# flipflop-edgedetect.net
KiCad netlist of a schematic drawn in EAGLE
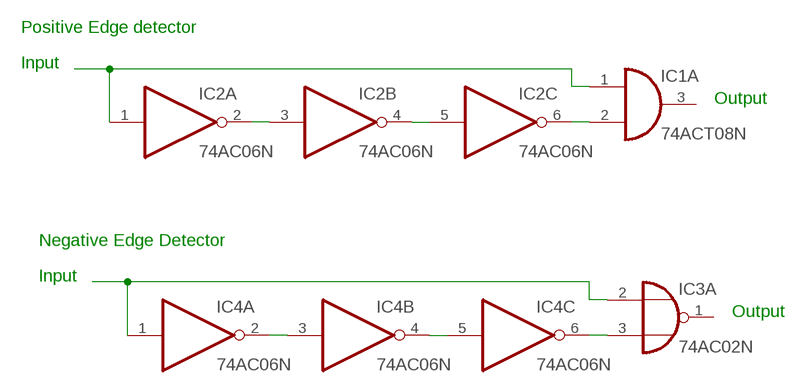
[diagram p0: schematic, sheet 1]

(export (version "E")
  (design (tool "Eeschema 10.0.6"))
  (components
    (comp (ref "IC1")
      (value "74ACT08N")
      (footprint "eagle-import:DIL14")
      (libsource (lib "eagle-import") (part "7408NACT"))
    )
    (comp (ref "IC2")
      (value "74AC06N")
      (footprint "eagle-import:DIL14")
      (libsource (lib "eagle-import") (part "7406NAC"))
    )
    (comp (ref "IC3")
      (value "74AC02N")
      (footprint "eagle-import:DIL14")
      (libsource (lib "eagle-import") (part "7402NAC"))
    )
    (comp (ref "IC4")
      (value "74AC06N")
      (footprint "eagle-import:DIL14")
      (libsource (lib "eagle-import") (part "7406NAC"))
    )
  )
  (nets
    (net (code "1") (name "Net-(IC1A-I0)") (class "Default")
      (node (ref "IC1") (pin "1") (pinfunction "I0_1") (pintype "input"))
      (node (ref "IC2") (pin "1") (pinfunction "I_1") (pintype "input"))
    )
    (net (code "2") (name "Net-(IC1A-I1)") (class "Default")
      (node (ref "IC1") (pin "2") (pinfunction "I1_2") (pintype "input"))
      (node (ref "IC2") (pin "6") (pinfunction "O_6") (pintype "open_collector"))
    )
    (net (code "3") (name "Net-(IC2A-O)") (class "Default")
      (node (ref "IC2") (pin "2") (pinfunction "O_2") (pintype "open_collector"))
      (node (ref "IC2") (pin "3") (pinfunction "I_3") (pintype "input"))
    )
    (net (code "4") (name "Net-(IC2B-O)") (class "Default")
      (node (ref "IC2") (pin "4") (pinfunction "O_4") (pintype "open_collector"))
      (node (ref "IC2") (pin "5") (pinfunction "I_5") (pintype "input"))
    )
    (net (code "5") (name "Net-(IC3A-I0)") (class "Default")
      (node (ref "IC3") (pin "2") (pinfunction "I0_2") (pintype "input"))
      (node (ref "IC4") (pin "1") (pinfunction "I_1") (pintype "input"))
    )
    (net (code "6") (name "Net-(IC3A-I1)") (class "Default")
      (node (ref "IC3") (pin "3") (pinfunction "I1_3") (pintype "input"))
      (node (ref "IC4") (pin "6") (pinfunction "O_6") (pintype "open_collector"))
    )
    (net (code "7") (name "Net-(IC4A-O)") (class "Default")
      (node (ref "IC4") (pin "2") (pinfunction "O_2") (pintype "open_collector"))
      (node (ref "IC4") (pin "3") (pinfunction "I_3") (pintype "input"))
    )
    (net (code "8") (name "Net-(IC4B-O)") (class "Default")
      (node (ref "IC4") (pin "4") (pinfunction "O_4") (pintype "open_collector"))
      (node (ref "IC4") (pin "5") (pinfunction "I_5") (pintype "input"))
    )
    (net (code "9") (name "unconnected-(IC1A-O-Pad3)") (class "Default")
      (node (ref "IC1") (pin "3") (pinfunction "O_3") (pintype "output"))
    )
    (net (code "10") (name "unconnected-(IC3A-O-Pad1)") (class "Default")
      (node (ref "IC3") (pin "1") (pinfunction "O_1") (pintype "output"))
    )
  )
)
